# mcu.net
KiCad netlist of a schematic drawn in Altium Designer
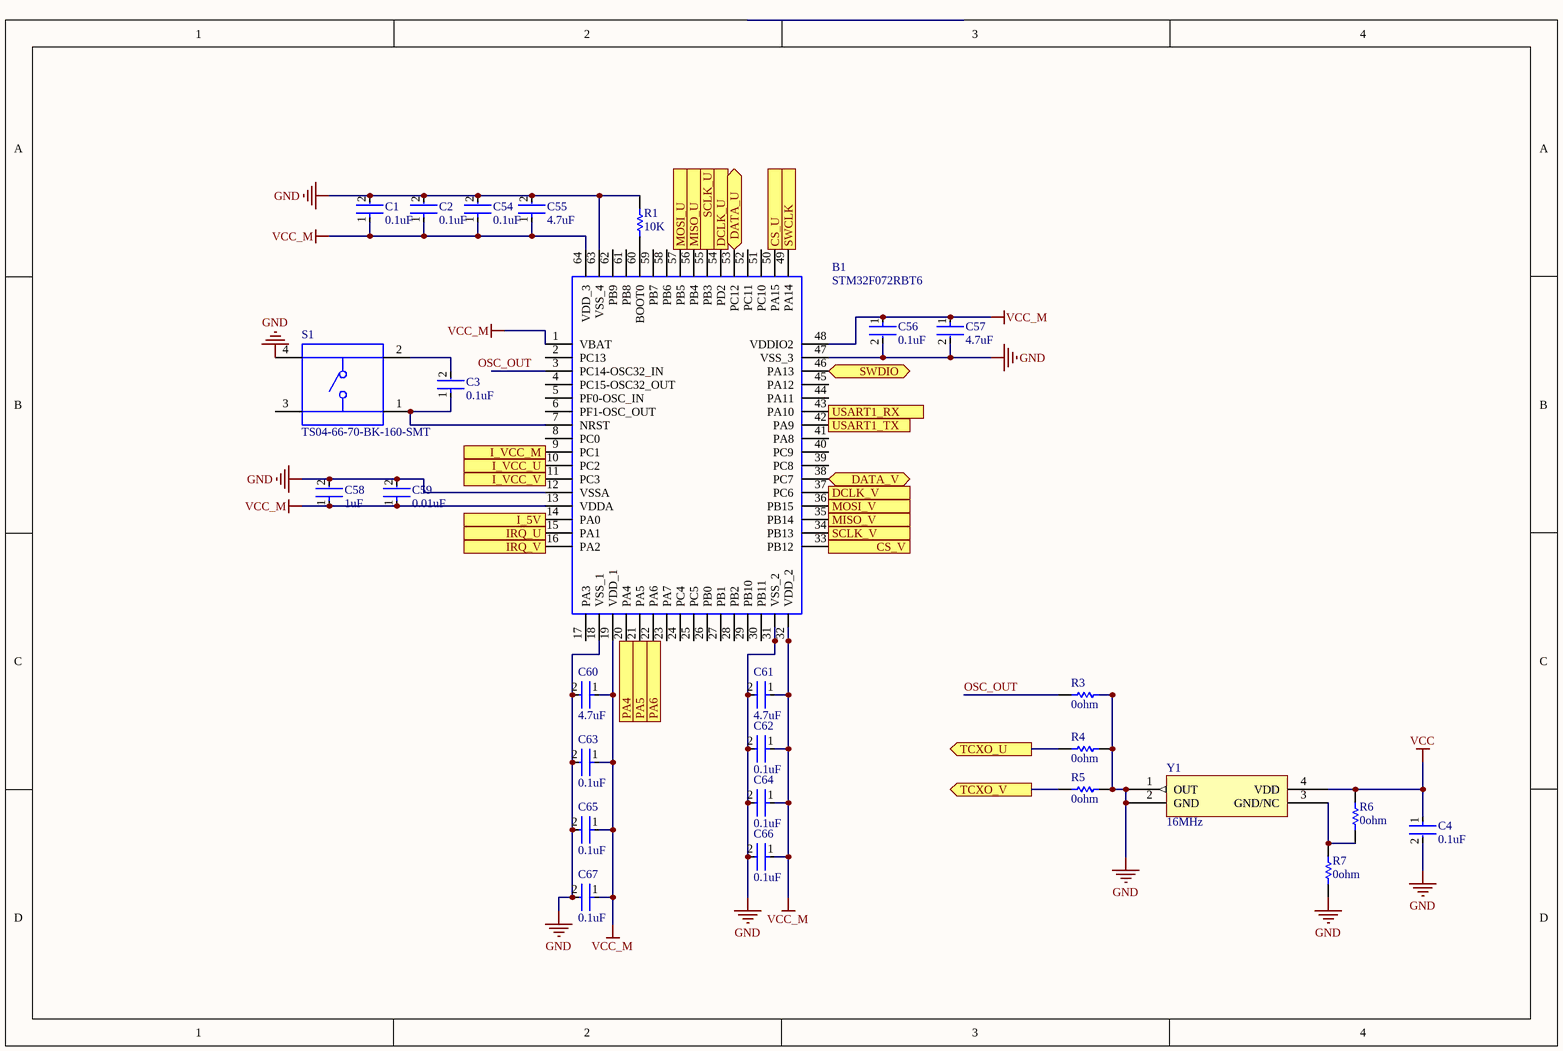
[diagram p0: mcu.SchDoc]

(export (version "E")
  (design (tool "Eeschema 10.0.6"))
  (components
    (comp (ref "B1")
      (value "STM32F072RBT6")
      (footprint "WEST_PCB_Library:QFP50P1200X1200X160-64N")
      (fields (field (name "MOUSER PART NUMBER") "511-STM32F072RBT6"))
      (libsource (lib "WEST_Schematic_Library") (part "STM32F072RBT6"))
    )
    (comp (ref "C1")
      (value "0.1uF")
      (footprint "FP-C0805C-DN-IPC_A")
      (description "Cap Ceramic 0.1uF 50V X7R 10% SMD 2.0 x 1.2 mm 125 C Paper T/R")
      (fields
        (field (name "MANUFACTURER") "KEMET")
        (field (name "MANUFACTURER PART NUMBER") "C0805C104K5RACTU")
      )
      (libsource (lib "WEST_Schematic_Library") (part "C0805C104K5RACTU"))
    )
    (comp (ref "C2")
      (value "0.1uF")
      (footprint "FP-C0805C-DN-IPC_A")
      (description "Cap Ceramic 0.1uF 50V X7R 10% SMD 2.0 x 1.2 mm 125 C Paper T/R")
      (fields
        (field (name "MANUFACTURER") "KEMET")
        (field (name "MANUFACTURER PART NUMBER") "C0805C104K5RACTU")
      )
      (libsource (lib "WEST_Schematic_Library") (part "C0805C104K5RACTU"))
    )
    (comp (ref "C3")
      (value "0.1uF")
      (footprint "FP-C0805C-DN-IPC_A")
      (description "Cap Ceramic 0.1uF 50V X7R 10% SMD 2.0 x 1.2 mm 125 C Paper T/R")
      (fields
        (field (name "MANUFACTURER") "KEMET")
        (field (name "MANUFACTURER PART NUMBER") "C0805C104K5RACTU")
      )
      (libsource (lib "WEST_Schematic_Library") (part "C0805C104K5RACTU"))
    )
    (comp (ref "C4")
      (value "0.1uF")
      (footprint "FP-C0805C-DN-IPC_A")
      (description "Cap Ceramic 0.1uF 50V X7R 10% SMD 2.0 x 1.2 mm 125 C Paper T/R")
      (fields
        (field (name "MANUFACTURER") "KEMET")
        (field (name "MANUFACTURER PART NUMBER") "C0805C104K5RACTU")
      )
      (libsource (lib "WEST_Schematic_Library") (part "C0805C104K5RACTU"))
    )
    (comp (ref "C54")
      (value "0.1uF")
      (footprint "FP-C0805C-DN-IPC_A")
      (description "Cap Ceramic 0.1uF 50V X7R 10% SMD 2.0 x 1.2 mm 125 C Paper T/R")
      (fields
        (field (name "MANUFACTURER") "KEMET")
        (field (name "MANUFACTURER PART NUMBER") "C0805C104K5RACTU")
      )
      (libsource (lib "WEST_Schematic_Library") (part "C0805C104K5RACTU"))
    )
    (comp (ref "C55")
      (value "4.7uF")
      (footprint "FP-C0805C-DN-IPC_A")
      (description "Cap Ceramic 4.7uF 25V X5R 10% SMD 0805 85°C Plastic T/R")
      (fields
        (field (name "MANUFACTURER") "KEMET")
        (field (name "MANUFACTURER PART NUMBER") "C0805C475K3PACTU")
      )
      (libsource (lib "WEST_Schematic_Library") (part "C0805C475K3PACTU"))
    )
    (comp (ref "C56")
      (value "0.1uF")
      (footprint "FP-C0805C-DN-IPC_A")
      (description "Cap Ceramic 0.1uF 50V X7R 10% SMD 2.0 x 1.2 mm 125 C Paper T/R")
      (fields
        (field (name "MANUFACTURER") "KEMET")
        (field (name "MANUFACTURER PART NUMBER") "C0805C104K5RACTU")
      )
      (libsource (lib "WEST_Schematic_Library") (part "C0805C104K5RACTU"))
    )
    (comp (ref "C57")
      (value "4.7uF")
      (footprint "FP-C0805C-DN-IPC_A")
      (description "Cap Ceramic 4.7uF 25V X5R 10% SMD 0805 85°C Plastic T/R")
      (fields
        (field (name "MANUFACTURER") "KEMET")
        (field (name "MANUFACTURER PART NUMBER") "C0805C475K3PACTU")
      )
      (libsource (lib "WEST_Schematic_Library") (part "C0805C475K3PACTU"))
    )
    (comp (ref "C58")
      (value "1uF")
      (footprint "FP-C0805C-DN-IPC_A")
      (description "Cap Ceramic 1uF 16V X5R 10% SMD 0805 85C Plastic T/R")
      (fields
        (field (name "MANUFACTURER") "KEMET")
        (field (name "MANUFACTURER PART NUMBER") "C0805C105K4PACTU")
      )
      (libsource (lib "WEST_Schematic_Library") (part "C0805C105K4PACTU"))
    )
    (comp (ref "C59")
      (value "0.01uF")
      (footprint "FP-C0805C-DN-IPC_A")
      (description "Cap Ceramic 0.01uF 50V X7R 10% SMD 0805 125C Plastic T/R")
      (fields
        (field (name "MANUFACTURER") "KEMET")
        (field (name "MANUFACTURER PART NUMBER") "C0805C103K5RAC-TU")
      )
      (libsource (lib "WEST_Schematic_Library") (part "C0805C103K5RAC-TU"))
    )
    (comp (ref "C60")
      (value "4.7uF")
      (footprint "FP-C0805C-DN-IPC_A")
      (description "Cap Ceramic 4.7uF 25V X5R 10% SMD 0805 85°C Plastic T/R")
      (fields
        (field (name "MANUFACTURER") "KEMET")
        (field (name "MANUFACTURER PART NUMBER") "C0805C475K3PACTU")
      )
      (libsource (lib "WEST_Schematic_Library") (part "C0805C475K3PACTU"))
    )
    (comp (ref "C61")
      (value "4.7uF")
      (footprint "FP-C0805C-DN-IPC_A")
      (description "Cap Ceramic 4.7uF 25V X5R 10% SMD 0805 85°C Plastic T/R")
      (fields
        (field (name "MANUFACTURER") "KEMET")
        (field (name "MANUFACTURER PART NUMBER") "C0805C475K3PACTU")
      )
      (libsource (lib "WEST_Schematic_Library") (part "C0805C475K3PACTU"))
    )
    (comp (ref "C62")
      (value "0.1uF")
      (footprint "FP-C0805C-DN-IPC_A")
      (description "Cap Ceramic 0.1uF 50V X7R 10% SMD 2.0 x 1.2 mm 125 C Paper T/R")
      (fields
        (field (name "MANUFACTURER") "KEMET")
        (field (name "MANUFACTURER PART NUMBER") "C0805C104K5RACTU")
      )
      (libsource (lib "WEST_Schematic_Library") (part "C0805C104K5RACTU"))
    )
    (comp (ref "C63")
      (value "0.1uF")
      (footprint "FP-C0805C-DN-IPC_A")
      (description "Cap Ceramic 0.1uF 50V X7R 10% SMD 2.0 x 1.2 mm 125 C Paper T/R")
      (fields
        (field (name "MANUFACTURER") "KEMET")
        (field (name "MANUFACTURER PART NUMBER") "C0805C104K5RACTU")
      )
      (libsource (lib "WEST_Schematic_Library") (part "C0805C104K5RACTU"))
    )
    (comp (ref "C64")
      (value "0.1uF")
      (footprint "FP-C0805C-DN-IPC_A")
      (description "Cap Ceramic 0.1uF 50V X7R 10% SMD 2.0 x 1.2 mm 125 C Paper T/R")
      (fields
        (field (name "MANUFACTURER") "KEMET")
        (field (name "MANUFACTURER PART NUMBER") "C0805C104K5RACTU")
      )
      (libsource (lib "WEST_Schematic_Library") (part "C0805C104K5RACTU"))
    )
    (comp (ref "C65")
      (value "0.1uF")
      (footprint "FP-C0805C-DN-IPC_A")
      (description "Cap Ceramic 0.1uF 50V X7R 10% SMD 2.0 x 1.2 mm 125 C Paper T/R")
      (fields
        (field (name "MANUFACTURER") "KEMET")
        (field (name "MANUFACTURER PART NUMBER") "C0805C104K5RACTU")
      )
      (libsource (lib "WEST_Schematic_Library") (part "C0805C104K5RACTU"))
    )
    (comp (ref "C66")
      (value "0.1uF")
      (footprint "FP-C0805C-DN-IPC_A")
      (description "Cap Ceramic 0.1uF 50V X7R 10% SMD 2.0 x 1.2 mm 125 C Paper T/R")
      (fields
        (field (name "MANUFACTURER") "KEMET")
        (field (name "MANUFACTURER PART NUMBER") "C0805C104K5RACTU")
      )
      (libsource (lib "WEST_Schematic_Library") (part "C0805C104K5RACTU"))
    )
    (comp (ref "C67")
      (value "0.1uF")
      (footprint "FP-C0805C-DN-IPC_A")
      (description "Cap Ceramic 0.1uF 50V X7R 10% SMD 2.0 x 1.2 mm 125 C Paper T/R")
      (fields
        (field (name "MANUFACTURER") "KEMET")
        (field (name "MANUFACTURER PART NUMBER") "C0805C104K5RACTU")
      )
      (libsource (lib "WEST_Schematic_Library") (part "C0805C104K5RACTU"))
    )
    (comp (ref "R1")
      (value "10K")
      (footprint "FP-C0805C-DN-IPC_A")
      (description "高精度、低温漂贴片电阻 10KΩ ±0.1% 1/8W ±25ppm/℃ 0805")
      (fields
        (field (name "MANUFACTURER") "Panasonic")
        (field (name "MANUFACTURER PART NUMBER") "ERA-6AEB103V")
      )
      (libsource (lib "WEST_Schematic_Library") (part "ERA-6AEB103V"))
    )
    (comp (ref "R3")
      (value "0ohm")
      (footprint "FP-C0805C-DN-IPC_A")
      (description "CRCW Series 0805 0.125 W 0 Ohm Jumper Surface Mount Thick Film Chip Resistor")
      (fields
        (field (name "MANUFACTURER") "Vishay")
        (field (name "MANUFACTURER PART NUMBER") "CRCW08050000Z0EA")
      )
      (libsource (lib "WEST_Schematic_Library") (part "CRCW08050000Z0EA"))
    )
    (comp (ref "R4")
      (value "0ohm")
      (footprint "FP-C0805C-DN-IPC_A")
      (description "CRCW Series 0805 0.125 W 0 Ohm Jumper Surface Mount Thick Film Chip Resistor")
      (fields
        (field (name "MANUFACTURER") "Vishay")
        (field (name "MANUFACTURER PART NUMBER") "CRCW08050000Z0EA")
      )
      (libsource (lib "WEST_Schematic_Library") (part "CRCW08050000Z0EA"))
    )
    (comp (ref "R5")
      (value "0ohm")
      (footprint "FP-C0805C-DN-IPC_A")
      (description "CRCW Series 0805 0.125 W 0 Ohm Jumper Surface Mount Thick Film Chip Resistor")
      (fields
        (field (name "MANUFACTURER") "Vishay")
        (field (name "MANUFACTURER PART NUMBER") "CRCW08050000Z0EA")
      )
      (libsource (lib "WEST_Schematic_Library") (part "CRCW08050000Z0EA"))
    )
    (comp (ref "R6")
      (value "0ohm")
      (footprint "FP-C0805C-DN-IPC_A")
      (description "CRCW Series 0805 0.125 W 0 Ohm Jumper Surface Mount Thick Film Chip Resistor")
      (fields
        (field (name "MANUFACTURER") "Vishay")
        (field (name "MANUFACTURER PART NUMBER") "CRCW08050000Z0EA")
      )
      (libsource (lib "WEST_Schematic_Library") (part "CRCW08050000Z0EA"))
    )
    (comp (ref "R7")
      (value "0ohm")
      (footprint "FP-C0805C-DN-IPC_A")
      (description "CRCW Series 0805 0.125 W 0 Ohm Jumper Surface Mount Thick Film Chip Resistor")
      (fields
        (field (name "MANUFACTURER") "Vishay")
        (field (name "MANUFACTURER PART NUMBER") "CRCW08050000Z0EA")
      )
      (libsource (lib "WEST_Schematic_Library") (part "CRCW08050000Z0EA"))
    )
    (comp (ref "S1")
      (value "TS04-66-70-BK-160-SMT")
      (footprint "SW_TS04-66-70-BK-160-SMT")
      (fields (field (name "MF") "{'manufacturer': u'CUI'}"))
      (libsource (lib "WEST_Schematic_Library") (part "TS04-66-70-BK-160-SMT"))
    )
    (comp (ref "Y1")
      (value "16MHz")
      (footprint "OSCCC320X250X100N")
      (description "Vctcxo @ 16.000MHZ, 2.8-3.3V, 2.5PPM")
      (fields
        (field (name "MANUFACTURER") "Taitien Electronics")
        (field (name "MANUFACTURER PART NUMBER") "TXETDDSANF-16.000000")
      )
      (libsource (lib "WEST_Schematic_Library") (part "TXETDDSANF-16.000000"))
    )
  )
  (nets
    (net (code "1") (name "/CS_U") (class "Default")
      (node (ref "B1") (pin "50") (pinfunction "PA15_50") (pintype "passive"))
    )
    (net (code "2") (name "/CS_V") (class "Default")
      (node (ref "B1") (pin "33") (pinfunction "PB12_33") (pintype "passive"))
    )
    (net (code "3") (name "/DATA_U") (class "Default")
      (node (ref "B1") (pin "53") (pinfunction "PC12_53") (pintype "passive"))
    )
    (net (code "4") (name "/DATA_V") (class "Default")
      (node (ref "B1") (pin "38") (pinfunction "PC7_38") (pintype "passive"))
    )
    (net (code "5") (name "/DCLK_U") (class "Default")
      (node (ref "B1") (pin "54") (pinfunction "PD2_54") (pintype "passive"))
    )
    (net (code "6") (name "/DCLK_V") (class "Default")
      (node (ref "B1") (pin "37") (pinfunction "PC6_37") (pintype "passive"))
    )
    (net (code "7") (name "/IRQ_U") (class "Default")
      (node (ref "B1") (pin "15") (pinfunction "PA1_15") (pintype "passive"))
    )
    (net (code "8") (name "/IRQ_V") (class "Default")
      (node (ref "B1") (pin "16") (pinfunction "PA2_16") (pintype "passive"))
    )
    (net (code "9") (name "/I_5V") (class "Default")
      (node (ref "B1") (pin "14") (pinfunction "PA0_14") (pintype "passive"))
    )
    (net (code "10") (name "/I_VCC_M") (class "Default")
      (node (ref "B1") (pin "9") (pinfunction "PC1_9") (pintype "passive"))
    )
    (net (code "11") (name "/I_VCC_U") (class "Default")
      (node (ref "B1") (pin "10") (pinfunction "PC2_10") (pintype "passive"))
    )
    (net (code "12") (name "/I_VCC_V") (class "Default")
      (node (ref "B1") (pin "11") (pinfunction "PC3_11") (pintype "passive"))
    )
    (net (code "13") (name "/MISO_U") (class "Default")
      (node (ref "B1") (pin "56") (pinfunction "PB4_56") (pintype "passive"))
    )
    (net (code "14") (name "/MISO_V") (class "Default")
      (node (ref "B1") (pin "35") (pinfunction "PB14_35") (pintype "passive"))
    )
    (net (code "15") (name "/MOSI_U") (class "Default")
      (node (ref "B1") (pin "57") (pinfunction "PB5_57") (pintype "passive"))
    )
    (net (code "16") (name "/MOSI_V") (class "Default")
      (node (ref "B1") (pin "36") (pinfunction "PB15_36") (pintype "passive"))
    )
    (net (code "17") (name "/OSC_OUT") (class "Default")
      (node (ref "R3") (pin "2") (pinfunction "2_2") (pintype "passive"))
    )
    (net (code "18") (name "/PA4") (class "Default")
      (node (ref "B1") (pin "20") (pinfunction "PA4_20") (pintype "passive"))
    )
    (net (code "19") (name "/PA5") (class "Default")
      (node (ref "B1") (pin "21") (pinfunction "PA5_21") (pintype "passive"))
    )
    (net (code "20") (name "/PA6") (class "Default")
      (node (ref "B1") (pin "22") (pinfunction "PA6_22") (pintype "passive"))
    )
    (net (code "21") (name "/SCLK_U") (class "Default")
      (node (ref "B1") (pin "55") (pinfunction "PB3_55") (pintype "passive"))
    )
    (net (code "22") (name "/SCLK_V") (class "Default")
      (node (ref "B1") (pin "34") (pinfunction "PB13_34") (pintype "passive"))
    )
    (net (code "23") (name "/SWCLK") (class "Default")
      (node (ref "B1") (pin "49") (pinfunction "PA14_49") (pintype "passive"))
    )
    (net (code "24") (name "/SWDIO") (class "Default")
      (node (ref "B1") (pin "46") (pinfunction "PA13_46") (pintype "passive"))
    )
    (net (code "25") (name "/TCXO_U") (class "Default")
      (node (ref "R4") (pin "2") (pinfunction "2_2") (pintype "passive"))
    )
    (net (code "26") (name "/TCXO_V") (class "Default")
      (node (ref "R5") (pin "1") (pinfunction "1_1") (pintype "passive"))
    )
    (net (code "27") (name "/USART1_RX") (class "Default")
      (node (ref "B1") (pin "43") (pinfunction "PA10_43") (pintype "passive"))
    )
    (net (code "28") (name "/USART1_TX") (class "Default")
      (node (ref "B1") (pin "42") (pinfunction "PA9_42") (pintype "passive"))
    )
    (net (code "29") (name "GND") (class "Default")
      (node (ref "B1") (pin "12") (pinfunction "VSSA_12") (pintype "passive"))
      (node (ref "B1") (pin "18") (pinfunction "VSS_1_18") (pintype "passive"))
      (node (ref "B1") (pin "31") (pinfunction "VSS_2_31") (pintype "passive"))
      (node (ref "B1") (pin "47") (pinfunction "VSS_3_47") (pintype "passive"))
      (node (ref "B1") (pin "63") (pinfunction "VSS_4_63") (pintype "passive"))
      (node (ref "C1") (pin "2") (pinfunction "2_2") (pintype "passive"))
      (node (ref "C2") (pin "2") (pinfunction "2_2") (pintype "passive"))
      (node (ref "C4") (pin "2") (pinfunction "2_2") (pintype "passive"))
      (node (ref "C54") (pin "2") (pinfunction "2_2") (pintype "passive"))
      (node (ref "C55") (pin "2") (pinfunction "2_2") (pintype "passive"))
      (node (ref "C56") (pin "2") (pinfunction "2_2") (pintype "passive"))
      (node (ref "C57") (pin "2") (pinfunction "2_2") (pintype "passive"))
      (node (ref "C58") (pin "2") (pinfunction "2_2") (pintype "passive"))
      (node (ref "C59") (pin "2") (pinfunction "2_2") (pintype "passive"))
      (node (ref "C60") (pin "2") (pinfunction "2_2") (pintype "passive"))
      (node (ref "C61") (pin "2") (pinfunction "2_2") (pintype "passive"))
      (node (ref "C62") (pin "2") (pinfunction "2_2") (pintype "passive"))
      (node (ref "C63") (pin "2") (pinfunction "2_2") (pintype "passive"))
      (node (ref "C64") (pin "2") (pinfunction "2_2") (pintype "passive"))
      (node (ref "C65") (pin "2") (pinfunction "2_2") (pintype "passive"))
      (node (ref "C66") (pin "2") (pinfunction "2_2") (pintype "passive"))
      (node (ref "C67") (pin "2") (pinfunction "2_2") (pintype "passive"))
      (node (ref "R1") (pin "2") (pinfunction "2_2") (pintype "passive"))
      (node (ref "R3") (pin "1") (pinfunction "1_1") (pintype "passive"))
      (node (ref "R4") (pin "1") (pinfunction "1_1") (pintype "passive"))
      (node (ref "R5") (pin "2") (pinfunction "2_2") (pintype "passive"))
      (node (ref "R7") (pin "2") (pinfunction "2_2") (pintype "passive"))
      (node (ref "S1") (pin "4") (pinfunction "4_4") (pintype "passive"))
      (node (ref "Y1") (pin "1") (pinfunction "OUT_1") (pintype "output"))
      (node (ref "Y1") (pin "2") (pinfunction "GND_2") (pintype "power_in"))
    )
    (net (code "30") (name "Net-(B1-BOOT0)") (class "Default")
      (node (ref "B1") (pin "60") (pinfunction "BOOT0_60") (pintype "passive"))
      (node (ref "R1") (pin "1") (pinfunction "1_1") (pintype "passive"))
    )
    (net (code "31") (name "Net-(B1-NRST)") (class "Default")
      (node (ref "B1") (pin "7") (pinfunction "NRST_7") (pintype "passive"))
      (node (ref "C3") (pin "1") (pinfunction "1_1") (pintype "passive"))
      (node (ref "S1") (pin "1") (pinfunction "1_1") (pintype "passive"))
    )
    (net (code "32") (name "Net-(C3-Pad2)") (class "Default")
      (node (ref "C3") (pin "2") (pinfunction "2_2") (pintype "passive"))
      (node (ref "S1") (pin "2") (pinfunction "2_2") (pintype "passive"))
    )
    (net (code "33") (name "Net-(Y1-GND{slash}NC)") (class "Default")
      (node (ref "R6") (pin "2") (pinfunction "2_2") (pintype "passive"))
      (node (ref "R7") (pin "1") (pinfunction "1_1") (pintype "passive"))
      (node (ref "Y1") (pin "3") (pinfunction "GND/NC_3") (pintype "power_in"))
    )
    (net (code "34") (name "VCC") (class "Default")
      (node (ref "C4") (pin "1") (pinfunction "1_1") (pintype "passive"))
      (node (ref "R6") (pin "1") (pinfunction "1_1") (pintype "passive"))
      (node (ref "Y1") (pin "4") (pinfunction "VDD_4") (pintype "power_in"))
    )
    (net (code "35") (name "VCC_M") (class "Default")
      (node (ref "B1") (pin "1") (pinfunction "VBAT_1") (pintype "passive"))
      (node (ref "B1") (pin "13") (pinfunction "VDDA_13") (pintype "passive"))
      (node (ref "B1") (pin "19") (pinfunction "VDD_1_19") (pintype "passive"))
      (node (ref "B1") (pin "32") (pinfunction "VDD_2_32") (pintype "passive"))
      (node (ref "B1") (pin "48") (pinfunction "VDDIO2_48") (pintype "passive"))
      (node (ref "B1") (pin "64") (pinfunction "VDD_3_64") (pintype "passive"))
      (node (ref "C1") (pin "1") (pinfunction "1_1") (pintype "passive"))
      (node (ref "C2") (pin "1") (pinfunction "1_1") (pintype "passive"))
      (node (ref "C54") (pin "1") (pinfunction "1_1") (pintype "passive"))
      (node (ref "C55") (pin "1") (pinfunction "1_1") (pintype "passive"))
      (node (ref "C56") (pin "1") (pinfunction "1_1") (pintype "passive"))
      (node (ref "C57") (pin "1") (pinfunction "1_1") (pintype "passive"))
      (node (ref "C58") (pin "1") (pinfunction "1_1") (pintype "passive"))
      (node (ref "C59") (pin "1") (pinfunction "1_1") (pintype "passive"))
      (node (ref "C60") (pin "1") (pinfunction "1_1") (pintype "passive"))
      (node (ref "C61") (pin "1") (pinfunction "1_1") (pintype "passive"))
      (node (ref "C62") (pin "1") (pinfunction "1_1") (pintype "passive"))
      (node (ref "C63") (pin "1") (pinfunction "1_1") (pintype "passive"))
      (node (ref "C64") (pin "1") (pinfunction "1_1") (pintype "passive"))
      (node (ref "C65") (pin "1") (pinfunction "1_1") (pintype "passive"))
      (node (ref "C66") (pin "1") (pinfunction "1_1") (pintype "passive"))
      (node (ref "C67") (pin "1") (pinfunction "1_1") (pintype "passive"))
    )
    (net (code "36") (name "unconnected-(B1-PA3-Pad17)") (class "Default")
      (node (ref "B1") (pin "17") (pinfunction "PA3_17") (pintype "passive"))
    )
    (net (code "37") (name "unconnected-(B1-PA7-Pad23)") (class "Default")
      (node (ref "B1") (pin "23") (pinfunction "PA7_23") (pintype "passive"))
    )
    (net (code "38") (name "unconnected-(B1-PA8-Pad41)") (class "Default")
      (node (ref "B1") (pin "41") (pinfunction "PA8_41") (pintype "passive"))
    )
    (net (code "39") (name "unconnected-(B1-PA11-Pad44)") (class "Default")
      (node (ref "B1") (pin "44") (pinfunction "PA11_44") (pintype "passive"))
    )
    (net (code "40") (name "unconnected-(B1-PA12-Pad45)") (class "Default")
      (node (ref "B1") (pin "45") (pinfunction "PA12_45") (pintype "passive"))
    )
    (net (code "41") (name "unconnected-(B1-PB0-Pad26)") (class "Default")
      (node (ref "B1") (pin "26") (pinfunction "PB0_26") (pintype "passive"))
    )
    (net (code "42") (name "unconnected-(B1-PB1-Pad27)") (class "Default")
      (node (ref "B1") (pin "27") (pinfunction "PB1_27") (pintype "passive"))
    )
    (net (code "43") (name "unconnected-(B1-PB2-Pad28)") (class "Default")
      (node (ref "B1") (pin "28") (pinfunction "PB2_28") (pintype "passive"))
    )
    (net (code "44") (name "unconnected-(B1-PB6-Pad58)") (class "Default")
      (node (ref "B1") (pin "58") (pinfunction "PB6_58") (pintype "passive"))
    )
    (net (code "45") (name "unconnected-(B1-PB7-Pad59)") (class "Default")
      (node (ref "B1") (pin "59") (pinfunction "PB7_59") (pintype "passive"))
    )
    (net (code "46") (name "unconnected-(B1-PB8-Pad61)") (class "Default")
      (node (ref "B1") (pin "61") (pinfunction "PB8_61") (pintype "passive"))
    )
    (net (code "47") (name "unconnected-(B1-PB9-Pad62)") (class "Default")
      (node (ref "B1") (pin "62") (pinfunction "PB9_62") (pintype "passive"))
    )
    (net (code "48") (name "unconnected-(B1-PB10-Pad29)") (class "Default")
      (node (ref "B1") (pin "29") (pinfunction "PB10_29") (pintype "passive"))
    )
    (net (code "49") (name "unconnected-(B1-PB11-Pad30)") (class "Default")
      (node (ref "B1") (pin "30") (pinfunction "PB11_30") (pintype "passive"))
    )
    (net (code "50") (name "unconnected-(B1-PC0-Pad8)") (class "Default")
      (node (ref "B1") (pin "8") (pinfunction "PC0_8") (pintype "passive"))
    )
    (net (code "51") (name "unconnected-(B1-PC4-Pad24)") (class "Default")
      (node (ref "B1") (pin "24") (pinfunction "PC4_24") (pintype "passive"))
    )
    (net (code "52") (name "unconnected-(B1-PC5-Pad25)") (class "Default")
      (node (ref "B1") (pin "25") (pinfunction "PC5_25") (pintype "passive"))
    )
    (net (code "53") (name "unconnected-(B1-PC8-Pad39)") (class "Default")
      (node (ref "B1") (pin "39") (pinfunction "PC8_39") (pintype "passive"))
    )
    (net (code "54") (name "unconnected-(B1-PC9-Pad40)") (class "Default")
      (node (ref "B1") (pin "40") (pinfunction "PC9_40") (pintype "passive"))
    )
    (net (code "55") (name "unconnected-(B1-PC10-Pad51)") (class "Default")
      (node (ref "B1") (pin "51") (pinfunction "PC10_51") (pintype "passive"))
    )
    (net (code "56") (name "unconnected-(B1-PC11-Pad52)") (class "Default")
      (node (ref "B1") (pin "52") (pinfunction "PC11_52") (pintype "passive"))
    )
    (net (code "57") (name "unconnected-(B1-PC13-Pad2)") (class "Default")
      (node (ref "B1") (pin "2") (pinfunction "PC13_2") (pintype "passive"))
    )
    (net (code "58") (name "unconnected-(B1-PC14-OSC32_IN-Pad3)") (class "Default")
      (node (ref "B1") (pin "3") (pinfunction "PC14-OSC32_IN_3") (pintype "passive"))
    )
    (net (code "59") (name "unconnected-(B1-PC15-OSC32_OUT-Pad4)") (class "Default")
      (node (ref "B1") (pin "4") (pinfunction "PC15-OSC32_OUT_4") (pintype "passive"))
    )
    (net (code "60") (name "unconnected-(B1-PF0-OSC_IN-Pad5)") (class "Default")
      (node (ref "B1") (pin "5") (pinfunction "PF0-OSC_IN_5") (pintype "passive"))
    )
    (net (code "61") (name "unconnected-(B1-PF1-OSC_OUT-Pad6)") (class "Default")
      (node (ref "B1") (pin "6") (pinfunction "PF1-OSC_OUT_6") (pintype "passive"))
    )
    (net (code "62") (name "unconnected-(S1-Pad3)") (class "Default")
      (node (ref "S1") (pin "3") (pinfunction "3_3") (pintype "passive"))
    )
  )
)
